# LiquidCrystal_SR1.net
KiCad netlist of a schematic drawn in EAGLE
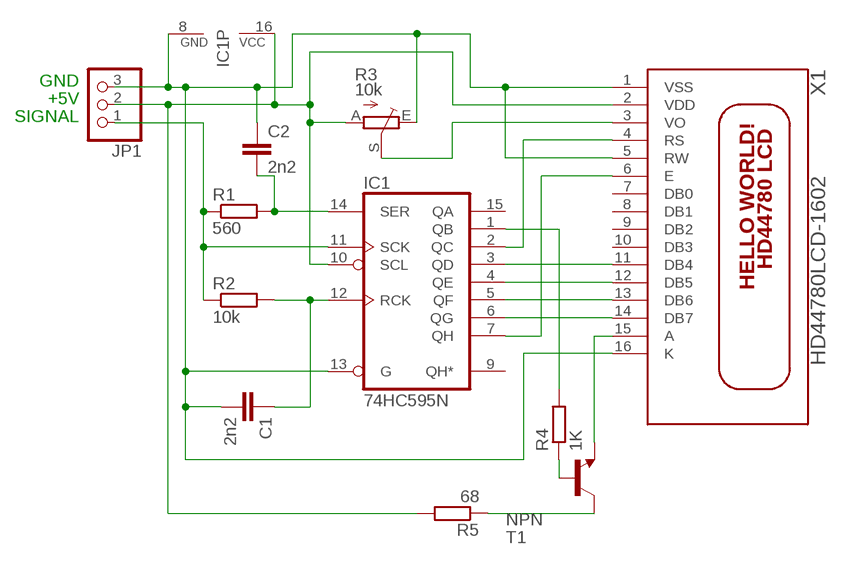
[diagram p0: schematic, sheet 1]

(export (version "E")
  (design (tool "Eeschema 10.0.6"))
  (components
    (comp (ref "C1")
      (value "2n2")
      (footprint "eagle-import:C025-050X050")
      (libsource (lib "eagle-import") (part "C-EU025-050X050"))
    )
    (comp (ref "C2")
      (value "2n2")
      (footprint "eagle-import:C025-050X050")
      (libsource (lib "eagle-import") (part "C-EU025-050X050"))
    )
    (comp (ref "IC1")
      (value "74HC595N")
      (footprint "eagle-import:DIL16")
      (libsource (lib "eagle-import") (part "74595NHC"))
    )
    (comp (ref "JP1")
      (value "PINHD-1X3")
      (footprint "eagle-import:1X03")
      (libsource (lib "eagle-import") (part "PINHD-1X3"))
    )
    (comp (ref "R1")
      (value "560")
      (footprint "eagle-import:0207_12")
      (libsource (lib "eagle-import") (part "R-EU_0207/12"))
    )
    (comp (ref "R2")
      (value "10k")
      (footprint "eagle-import:0207_12")
      (libsource (lib "eagle-import") (part "R-EU_0207/12"))
    )
    (comp (ref "R3")
      (value "10k")
      (footprint "eagle-import:CA6V")
      (libsource (lib "eagle-import") (part "TRIM_EU-CA6V"))
    )
    (comp (ref "R4")
      (value "1K")
      (footprint "eagle-import:0207_12")
      (libsource (lib "eagle-import") (part "R-EU_0207/12"))
    )
    (comp (ref "R5")
      (value "68")
      (footprint "eagle-import:0207_12")
      (libsource (lib "eagle-import") (part "R-EU_0207/12"))
    )
    (comp (ref "T1")
      (value "NPN")
      (footprint "eagle-import:TO92-EBC")
      (libsource (lib "eagle-import") (part "-NPN-TO92-EBC"))
    )
    (comp (ref "X1")
      (value "HD44780LCD-1602")
      (footprint "eagle-import:LCD1602")
      (libsource (lib "eagle-import") (part "HD44780LCD-1602"))
    )
  )
  (nets
    (net (code "1") (name "Net-(IC1A-G)") (class "Default")
      (node (ref "C1") (pin "2") (pinfunction "2_2") (pintype "passive"))
      (node (ref "C2") (pin "1") (pinfunction "1_1") (pintype "passive"))
      (node (ref "IC1") (pin "13") (pinfunction "G_13") (pintype "input"))
      (node (ref "IC1") (pin "8") (pinfunction "GND_8") (pintype "power_in"))
      (node (ref "JP1") (pin "3") (pinfunction "3_3") (pintype "passive"))
      (node (ref "R3") (pin "E") (pinfunction "E_E") (pintype "passive"))
      (node (ref "X1") (pin "1") (pinfunction "VSS_1") (pintype "power_in"))
      (node (ref "X1") (pin "16") (pinfunction "K_16") (pintype "input"))
      (node (ref "X1") (pin "5") (pinfunction "RW_5") (pintype "input"))
    )
    (net (code "2") (name "Net-(IC1A-QB)") (class "Default")
      (node (ref "IC1") (pin "1") (pinfunction "QB_1") (pintype "tri_state"))
      (node (ref "R4") (pin "2") (pinfunction "2_2") (pintype "passive"))
    )
    (net (code "3") (name "Net-(IC1A-QC)") (class "Default")
      (node (ref "IC1") (pin "2") (pinfunction "QC_2") (pintype "tri_state"))
      (node (ref "X1") (pin "4") (pinfunction "RS_4") (pintype "input"))
    )
    (net (code "4") (name "Net-(IC1A-QD)") (class "Default")
      (node (ref "IC1") (pin "3") (pinfunction "QD_3") (pintype "tri_state"))
      (node (ref "X1") (pin "11") (pinfunction "DB4_11") (pintype "bidirectional"))
    )
    (net (code "5") (name "Net-(IC1A-QE)") (class "Default")
      (node (ref "IC1") (pin "4") (pinfunction "QE_4") (pintype "tri_state"))
      (node (ref "X1") (pin "12") (pinfunction "DB5_12") (pintype "bidirectional"))
    )
    (net (code "6") (name "Net-(IC1A-QF)") (class "Default")
      (node (ref "IC1") (pin "5") (pinfunction "QF_5") (pintype "tri_state"))
      (node (ref "X1") (pin "13") (pinfunction "DB6_13") (pintype "bidirectional"))
    )
    (net (code "7") (name "Net-(IC1A-QG)") (class "Default")
      (node (ref "IC1") (pin "6") (pinfunction "QG_6") (pintype "tri_state"))
      (node (ref "X1") (pin "14") (pinfunction "DB7_14") (pintype "bidirectional"))
    )
    (net (code "8") (name "Net-(IC1A-QH)") (class "Default")
      (node (ref "IC1") (pin "7") (pinfunction "QH_7") (pintype "tri_state"))
      (node (ref "X1") (pin "6") (pinfunction "E_6") (pintype "input"))
    )
    (net (code "9") (name "Net-(IC1A-RCK)") (class "Default")
      (node (ref "C1") (pin "1") (pinfunction "1_1") (pintype "passive"))
      (node (ref "IC1") (pin "12") (pinfunction "RCK_12") (pintype "input"))
      (node (ref "R2") (pin "2") (pinfunction "2_2") (pintype "passive"))
    )
    (net (code "10") (name "Net-(IC1A-SCK)") (class "Default")
      (node (ref "IC1") (pin "11") (pinfunction "SCK_11") (pintype "input"))
      (node (ref "JP1") (pin "1") (pinfunction "1_1") (pintype "passive"))
      (node (ref "R1") (pin "1") (pinfunction "1_1") (pintype "passive"))
      (node (ref "R2") (pin "1") (pinfunction "1_1") (pintype "passive"))
    )
    (net (code "11") (name "Net-(IC1A-SCL)") (class "Default")
      (node (ref "IC1") (pin "10") (pinfunction "SCL_10") (pintype "input"))
      (node (ref "IC1") (pin "16") (pinfunction "VCC_16") (pintype "power_in"))
      (node (ref "JP1") (pin "2") (pinfunction "2_2") (pintype "passive"))
      (node (ref "R3") (pin "A") (pinfunction "A_A") (pintype "passive"))
      (node (ref "R5") (pin "2") (pinfunction "2_2") (pintype "passive"))
      (node (ref "X1") (pin "2") (pinfunction "VDD_2") (pintype "power_in"))
    )
    (net (code "12") (name "Net-(IC1A-SER)") (class "Default")
      (node (ref "C2") (pin "2") (pinfunction "2_2") (pintype "passive"))
      (node (ref "IC1") (pin "14") (pinfunction "SER_14") (pintype "input"))
      (node (ref "R1") (pin "2") (pinfunction "2_2") (pintype "passive"))
    )
    (net (code "13") (name "Net-(R4-Pad1)") (class "Default")
      (node (ref "R4") (pin "1") (pinfunction "1_1") (pintype "passive"))
      (node (ref "T1") (pin "B") (pinfunction "B_B") (pintype "passive"))
    )
    (net (code "14") (name "Net-(R5-Pad1)") (class "Default")
      (node (ref "R5") (pin "1") (pinfunction "1_1") (pintype "passive"))
      (node (ref "T1") (pin "C") (pinfunction "C_C") (pintype "passive"))
    )
    (net (code "15") (name "Net-(X1-A)") (class "Default")
      (node (ref "T1") (pin "E") (pinfunction "E_E") (pintype "passive"))
      (node (ref "X1") (pin "15") (pinfunction "A_15") (pintype "input"))
    )
    (net (code "16") (name "Net-(X1-VO)") (class "Default")
      (node (ref "R3") (pin "S") (pinfunction "S_S") (pintype "passive"))
      (node (ref "X1") (pin "3") (pinfunction "VO_3") (pintype "input"))
    )
    (net (code "17") (name "unconnected-(IC1A-QA-Pad15)") (class "Default")
      (node (ref "IC1") (pin "15") (pinfunction "QA_15") (pintype "tri_state"))
    )
    (net (code "18") (name "unconnected-(IC1A-QH*-Pad9)") (class "Default")
      (node (ref "IC1") (pin "9") (pinfunction "QH*_9") (pintype "tri_state"))
    )
    (net (code "19") (name "unconnected-(X1-DB0-Pad7)") (class "Default")
      (node (ref "X1") (pin "7") (pinfunction "DB0_7") (pintype "bidirectional"))
    )
    (net (code "20") (name "unconnected-(X1-DB1-Pad8)") (class "Default")
      (node (ref "X1") (pin "8") (pinfunction "DB1_8") (pintype "bidirectional"))
    )
    (net (code "21") (name "unconnected-(X1-DB2-Pad9)") (class "Default")
      (node (ref "X1") (pin "9") (pinfunction "DB2_9") (pintype "bidirectional"))
    )
    (net (code "22") (name "unconnected-(X1-DB3-Pad10)") (class "Default")
      (node (ref "X1") (pin "10") (pinfunction "DB3_10") (pintype "bidirectional"))
    )
  )
)
